# DynInd.net
KiCad netlist of a schematic drawn in EasyEDA
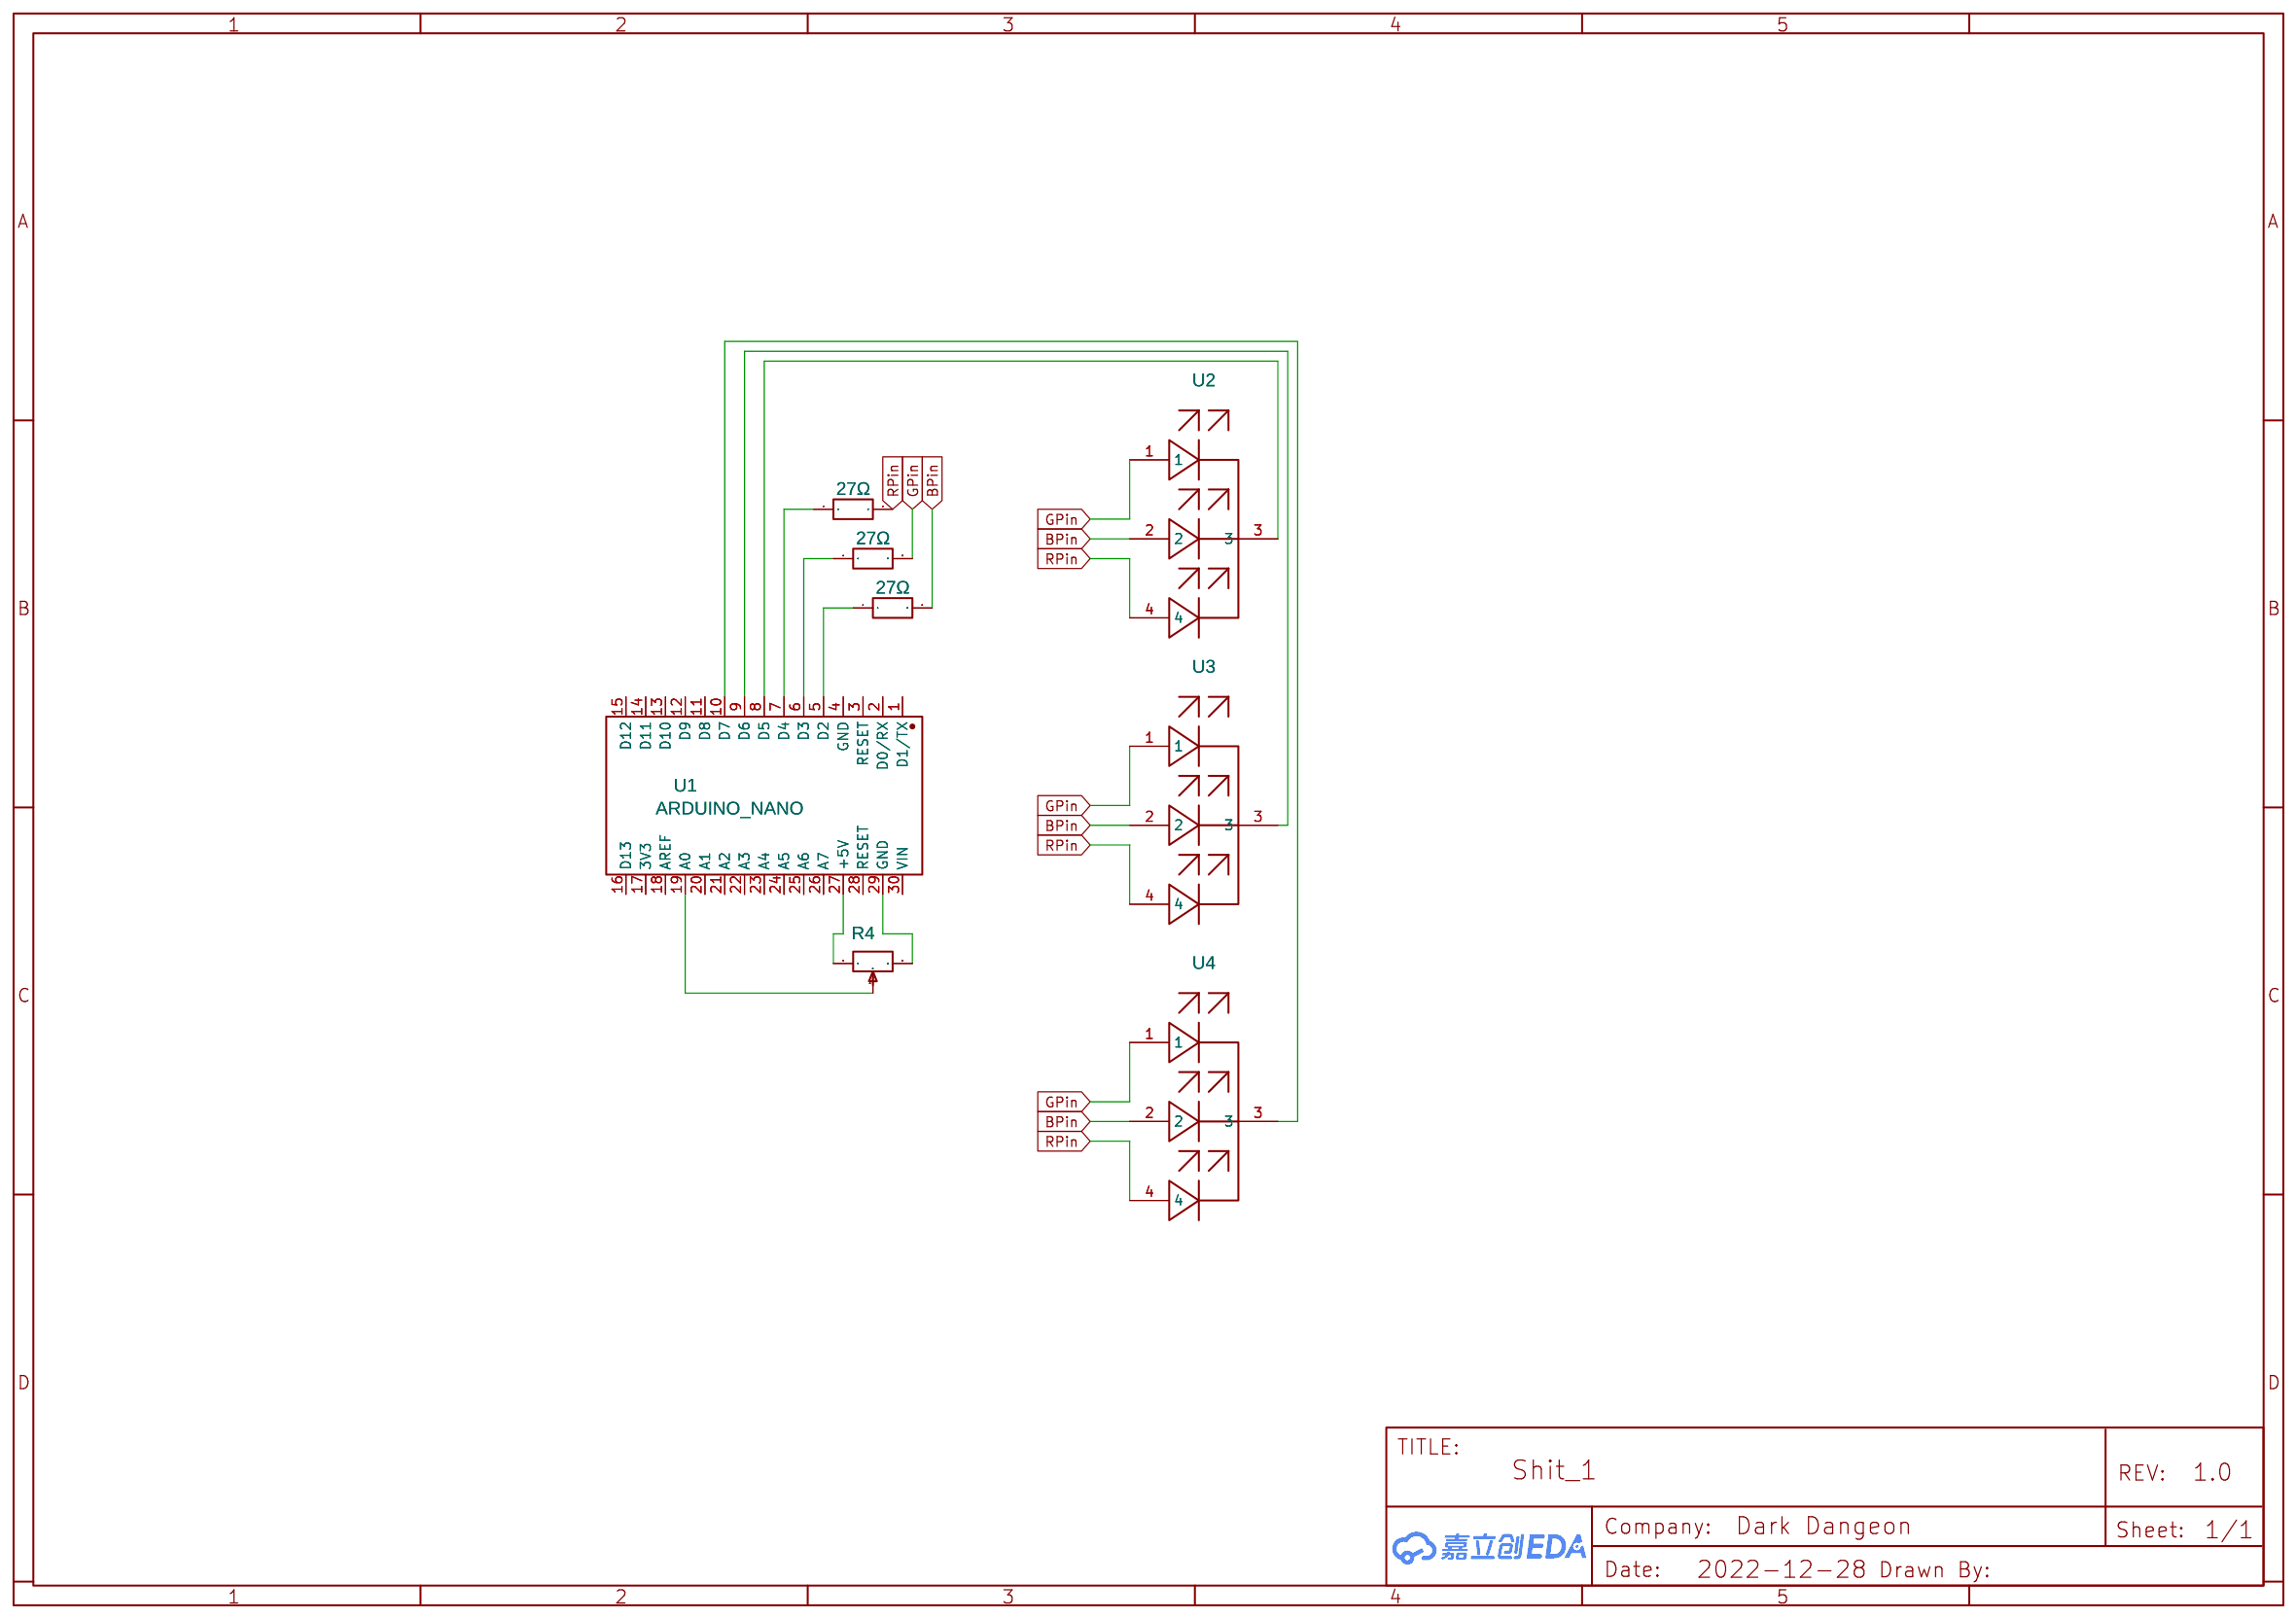
[diagram p0: schematic sheet]

(export (version "E")
  (design (tool "Eeschema 10.0.6"))
  (components
    (comp (ref "R1") (value "27Ω") (libsource (lib "") (part "R_0603_EU")))
    (comp (ref "R2") (value "27Ω") (libsource (lib "") (part "R_0603_EU")))
    (comp (ref "R3") (value "27Ω") (libsource (lib "") (part "R_0603_EU")))
    (comp (ref "R4")
      (value "Precision potentiometer 3296W/50ohm")
      (fields (field (name "BOM_Supplier Part") "C21881"))
      (libsource (lib "") (part "Precision potentiometer 3296W/50ohm"))
    )
    (comp (ref "U1")
      (value "ARDUINO_NANO")
      (fields (field (name "BOM_Supplier Part") "C9900017879"))
      (libsource (lib "") (part "ARDUINO_NANO"))
    )
    (comp (ref "U2") (value "LED_BL-L515RGBW") (libsource (lib "") (part "LED_BL-L515RGBW")))
    (comp (ref "U3") (value "LED_BL-L515RGBW") (libsource (lib "") (part "LED_BL-L515RGBW")))
    (comp (ref "U4") (value "LED_BL-L515RGBW") (libsource (lib "") (part "LED_BL-L515RGBW")))
  )
  (nets
    (net (code "1") (name "BPin") (class "Default")
      (node (ref "R3") (pin "2") (pinfunction "2_2") (pintype "unspecified"))
      (node (ref "U2") (pin "2") (pinfunction "2_2") (pintype "unspecified"))
      (node (ref "U3") (pin "2") (pinfunction "2_2") (pintype "unspecified"))
      (node (ref "U4") (pin "2") (pinfunction "2_2") (pintype "unspecified"))
    )
    (net (code "2") (name "GPin") (class "Default")
      (node (ref "R2") (pin "2") (pinfunction "2_2") (pintype "unspecified"))
      (node (ref "U2") (pin "1") (pinfunction "1_1") (pintype "unspecified"))
      (node (ref "U3") (pin "1") (pinfunction "1_1") (pintype "unspecified"))
      (node (ref "U4") (pin "1") (pinfunction "1_1") (pintype "unspecified"))
    )
    (net (code "3") (name "Net-(R4-Pad3)") (class "Default")
      (node (ref "R4") (pin "3") (pinfunction "3_3") (pintype "input"))
      (node (ref "U1") (pin "29") (pinfunction "GND_29") (pintype "unspecified"))
    )
    (net (code "4") (name "Net-(U1-+5V)") (class "Default")
      (node (ref "R4") (pin "1") (pinfunction "1_1") (pintype "input"))
      (node (ref "U1") (pin "27") (pinfunction "+5V_27") (pintype "unspecified"))
    )
    (net (code "5") (name "Net-(U1-A0)") (class "Default")
      (node (ref "R4") (pin "2") (pinfunction "2_2") (pintype "input"))
      (node (ref "U1") (pin "19") (pinfunction "A0_19") (pintype "unspecified"))
    )
    (net (code "6") (name "Net-(U1-D2)") (class "Default")
      (node (ref "R3") (pin "1") (pinfunction "1_1") (pintype "unspecified"))
      (node (ref "U1") (pin "5") (pinfunction "D2_5") (pintype "unspecified"))
    )
    (net (code "7") (name "Net-(U1-D3)") (class "Default")
      (node (ref "R2") (pin "1") (pinfunction "1_1") (pintype "unspecified"))
      (node (ref "U1") (pin "6") (pinfunction "D3_6") (pintype "unspecified"))
    )
    (net (code "8") (name "Net-(U1-D4)") (class "Default")
      (node (ref "R1") (pin "1") (pinfunction "1_1") (pintype "unspecified"))
      (node (ref "U1") (pin "7") (pinfunction "D4_7") (pintype "unspecified"))
    )
    (net (code "9") (name "Net-(U1-D5)") (class "Default")
      (node (ref "U1") (pin "8") (pinfunction "D5_8") (pintype "unspecified"))
      (node (ref "U2") (pin "3") (pinfunction "3_3") (pintype "unspecified"))
    )
    (net (code "10") (name "Net-(U1-D6)") (class "Default")
      (node (ref "U1") (pin "9") (pinfunction "D6_9") (pintype "unspecified"))
      (node (ref "U3") (pin "3") (pinfunction "3_3") (pintype "unspecified"))
    )
    (net (code "11") (name "Net-(U1-D7)") (class "Default")
      (node (ref "U1") (pin "10") (pinfunction "D7_10") (pintype "unspecified"))
      (node (ref "U4") (pin "3") (pinfunction "3_3") (pintype "unspecified"))
    )
    (net (code "12") (name "RPin") (class "Default")
      (node (ref "R1") (pin "2") (pinfunction "2_2") (pintype "unspecified"))
      (node (ref "U2") (pin "4") (pinfunction "4_4") (pintype "unspecified"))
      (node (ref "U3") (pin "4") (pinfunction "4_4") (pintype "unspecified"))
      (node (ref "U4") (pin "4") (pinfunction "4_4") (pintype "unspecified"))
    )
    (net (code "13") (name "unconnected-(U1-3V3-Pad17)") (class "Default")
      (node (ref "U1") (pin "17") (pinfunction "3V3_17") (pintype "unspecified"))
    )
    (net (code "14") (name "unconnected-(U1-A1-Pad20)") (class "Default")
      (node (ref "U1") (pin "20") (pinfunction "A1_20") (pintype "unspecified"))
    )
    (net (code "15") (name "unconnected-(U1-A2-Pad21)") (class "Default")
      (node (ref "U1") (pin "21") (pinfunction "A2_21") (pintype "unspecified"))
    )
    (net (code "16") (name "unconnected-(U1-A3-Pad22)") (class "Default")
      (node (ref "U1") (pin "22") (pinfunction "A3_22") (pintype "unspecified"))
    )
    (net (code "17") (name "unconnected-(U1-A4-Pad23)") (class "Default")
      (node (ref "U1") (pin "23") (pinfunction "A4_23") (pintype "unspecified"))
    )
    (net (code "18") (name "unconnected-(U1-A5-Pad24)") (class "Default")
      (node (ref "U1") (pin "24") (pinfunction "A5_24") (pintype "unspecified"))
    )
    (net (code "19") (name "unconnected-(U1-A6-Pad25)") (class "Default")
      (node (ref "U1") (pin "25") (pinfunction "A6_25") (pintype "unspecified"))
    )
    (net (code "20") (name "unconnected-(U1-A7-Pad26)") (class "Default")
      (node (ref "U1") (pin "26") (pinfunction "A7_26") (pintype "unspecified"))
    )
    (net (code "21") (name "unconnected-(U1-AREF-Pad18)") (class "Default")
      (node (ref "U1") (pin "18") (pinfunction "AREF_18") (pintype "unspecified"))
    )
    (net (code "22") (name "unconnected-(U1-D0{slash}RX-Pad2)") (class "Default")
      (node (ref "U1") (pin "2") (pinfunction "D0/RX_2") (pintype "unspecified"))
    )
    (net (code "23") (name "unconnected-(U1-D1{slash}TX-Pad1)") (class "Default")
      (node (ref "U1") (pin "1") (pinfunction "D1/TX_1") (pintype "unspecified"))
    )
    (net (code "24") (name "unconnected-(U1-D8-Pad11)") (class "Default")
      (node (ref "U1") (pin "11") (pinfunction "D8_11") (pintype "unspecified"))
    )
    (net (code "25") (name "unconnected-(U1-D9-Pad12)") (class "Default")
      (node (ref "U1") (pin "12") (pinfunction "D9_12") (pintype "unspecified"))
    )
    (net (code "26") (name "unconnected-(U1-D10-Pad13)") (class "Default")
      (node (ref "U1") (pin "13") (pinfunction "D10_13") (pintype "unspecified"))
    )
    (net (code "27") (name "unconnected-(U1-D11-Pad14)") (class "Default")
      (node (ref "U1") (pin "14") (pinfunction "D11_14") (pintype "unspecified"))
    )
    (net (code "28") (name "unconnected-(U1-D12-Pad15)") (class "Default")
      (node (ref "U1") (pin "15") (pinfunction "D12_15") (pintype "unspecified"))
    )
    (net (code "29") (name "unconnected-(U1-D13-Pad16)") (class "Default")
      (node (ref "U1") (pin "16") (pinfunction "D13_16") (pintype "unspecified"))
    )
    (net (code "30") (name "unconnected-(U1-GND-Pad4)") (class "Default")
      (node (ref "U1") (pin "4") (pinfunction "GND_4") (pintype "unspecified"))
    )
    (net (code "31") (name "unconnected-(U1-RESET-Pad3)") (class "Default")
      (node (ref "U1") (pin "3") (pinfunction "RESET_3") (pintype "unspecified"))
    )
    (net (code "32") (name "unconnected-(U1-RESET-Pad28)") (class "Default")
      (node (ref "U1") (pin "28") (pinfunction "RESET_28") (pintype "unspecified"))
    )
    (net (code "33") (name "unconnected-(U1-VIN-Pad30)") (class "Default")
      (node (ref "U1") (pin "30") (pinfunction "VIN_30") (pintype "unspecified"))
    )
  )
)
